# mcu.net
KiCad netlist of a schematic drawn in Altium Designer
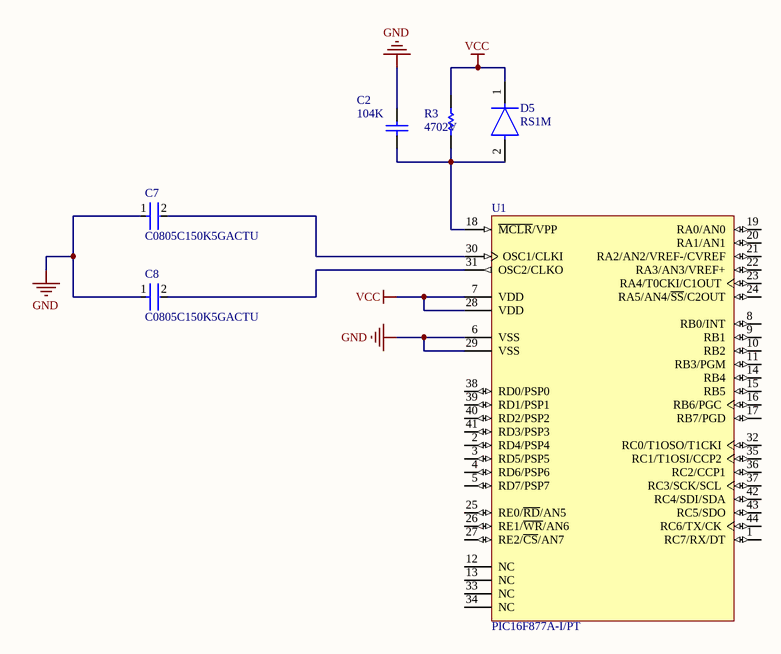
[diagram p0: mcu.SchDoc]

(export (version "E")
  (design (tool "Eeschema 10.0.6"))
  (components
    (comp (ref "C2")
      (value "104K")
      (footprint "CAPC2013X88X50NL20T25")
      (fields (field (name "PART NUMBER") "C0805C104K5RACTU") (field (name "MANUFACTURER") "Kemet"))
      (libsource (lib "Altium Content Vault") (part "CAP"))
    )
    (comp (ref "C7")
      (value "C0805C150K5GACTU")
      (footprint "FP-C0805C-DN-MFG")
      (description "CAP CER 15PF 50V 10% NP0 0805")
      (fields
        (field (name "MANUFACTURER") "KEMET")
        (field (name "OCTOPART") "https://octopart.com/c0805c150k5gactu-kemet-6813460")
      )
      (libsource (lib "Altium Content Vault") (part "b4654b650e69147ec39a6b967a45e02"))
    )
    (comp (ref "C8")
      (value "C0805C150K5GACTU")
      (footprint "FP-C0805C-DN-MFG")
      (description "CAP CER 15PF 50V 10% NP0 0805")
      (fields
        (field (name "MANUFACTURER") "KEMET")
        (field (name "OCTOPART") "https://octopart.com/c0805c150k5gactu-kemet-6813460")
      )
      (libsource (lib "Altium Content Vault") (part "b4654b650e69147ec39a6b967a45e02"))
    )
    (comp (ref "D5")
      (value "RS1M")
      (footprint "FP-403AE-MFG")
      (description "DIODE GEN PURP 1KV 1A SMA")
      (fields
        (field (name "OCTOPART") "https://octopart.com/rs1m-on+semiconductor-84331238")
        (field (name "MANUFACTURER") "ON Semiconductor")
      )
      (libsource (lib "Altium Content Vault") (part "d7152d700b627762746794eb795d46e"))
    )
    (comp (ref "R3")
      (value "4702V")
      (footprint "RESC2013X70X40LL20T20")
      (fields (field (name "MANUFACTURER") "Panasonic") (field (name "PART NUMBER") "ERJ6ENF4702V"))
      (libsource (lib "Altium Content Vault") (part "RES"))
    )
    (comp (ref "U1")
      (value "PIC16F877A-I/PT")
      (footprint "TQFP-PT44_M")
      (libsource (lib "Altium Content Vault") (part "MC-8B-16F874A-SQ44B"))
    )
  )
  (nets
    (net (code "1") (name "GND") (class "Default")
      (node (ref "C2") (pin "2") (pinfunction "2_2") (pintype "passive"))
      (node (ref "C7") (pin "1") (pinfunction "1_1") (pintype "passive"))
      (node (ref "C8") (pin "1") (pinfunction "1_1") (pintype "passive"))
      (node (ref "U1") (pin "29") (pinfunction "VSS_29") (pintype "power_in"))
      (node (ref "U1") (pin "6") (pinfunction "VSS_6") (pintype "power_in"))
    )
    (net (code "2") (name "Net-(D5-A)") (class "Default")
      (node (ref "C2") (pin "1") (pinfunction "1_1") (pintype "passive"))
      (node (ref "D5") (pin "2") (pinfunction "A_2") (pintype "passive"))
      (node (ref "R3") (pin "1") (pinfunction "1_1") (pintype "passive"))
      (node (ref "U1") (pin "18") (pinfunction "~{MCLR}/VPP_18") (pintype "input"))
    )
    (net (code "3") (name "Net-(U1-OSC1{slash}CLKI)") (class "Default")
      (node (ref "C7") (pin "2") (pinfunction "2_2") (pintype "passive"))
      (node (ref "U1") (pin "30") (pinfunction "OSC1/CLKI_30") (pintype "input"))
    )
    (net (code "4") (name "Net-(U1-OSC2{slash}CLKO)") (class "Default")
      (node (ref "C8") (pin "2") (pinfunction "2_2") (pintype "passive"))
      (node (ref "U1") (pin "31") (pinfunction "OSC2/CLKO_31") (pintype "output"))
    )
    (net (code "5") (name "VCC") (class "Default")
      (node (ref "D5") (pin "1") (pinfunction "C_1") (pintype "passive"))
      (node (ref "R3") (pin "2") (pinfunction "2_2") (pintype "passive"))
      (node (ref "U1") (pin "28") (pinfunction "VDD_28") (pintype "power_in"))
      (node (ref "U1") (pin "7") (pinfunction "VDD_7") (pintype "power_in"))
    )
    (net (code "6") (name "unconnected-(U1-NC-Pad12)") (class "Default")
      (node (ref "U1") (pin "12") (pinfunction "NC_12") (pintype "passive"))
    )
    (net (code "7") (name "unconnected-(U1-NC-Pad13)") (class "Default")
      (node (ref "U1") (pin "13") (pinfunction "NC_13") (pintype "passive"))
    )
    (net (code "8") (name "unconnected-(U1-NC-Pad33)") (class "Default")
      (node (ref "U1") (pin "33") (pinfunction "NC_33") (pintype "passive"))
    )
    (net (code "9") (name "unconnected-(U1-NC-Pad34)") (class "Default")
      (node (ref "U1") (pin "34") (pinfunction "NC_34") (pintype "passive"))
    )
    (net (code "10") (name "unconnected-(U1-RA0{slash}AN0-Pad19)") (class "Default")
      (node (ref "U1") (pin "19") (pinfunction "RA0/AN0_19") (pintype "bidirectional"))
    )
    (net (code "11") (name "unconnected-(U1-RA1{slash}AN1-Pad20)") (class "Default")
      (node (ref "U1") (pin "20") (pinfunction "RA1/AN1_20") (pintype "bidirectional"))
    )
    (net (code "12") (name "unconnected-(U1-RA2{slash}AN2{slash}VREF-{slash}CVREF-Pad21)") (class "Default")
      (node (ref "U1") (pin "21") (pinfunction "RA2/AN2/VREF-/CVREF_21") (pintype "bidirectional"))
    )
    (net (code "13") (name "unconnected-(U1-RA3{slash}AN3{slash}VREF+-Pad22)") (class "Default")
      (node (ref "U1") (pin "22") (pinfunction "RA3/AN3/VREF+_22") (pintype "bidirectional"))
    )
    (net (code "14") (name "unconnected-(U1-RA4{slash}T0CKI{slash}C1OUT-Pad23)") (class "Default")
      (node (ref "U1") (pin "23") (pinfunction "RA4/T0CKI/C1OUT_23") (pintype "bidirectional"))
    )
    (net (code "15") (name "unconnected-(U1-RA5{slash}AN4{slash}~{SS}{slash}C2OUT-Pad24)") (class "Default")
      (node (ref "U1") (pin "24") (pinfunction "RA5/AN4/~{SS}/C2OUT_24") (pintype "bidirectional"))
    )
    (net (code "16") (name "unconnected-(U1-RB0{slash}INT-Pad8)") (class "Default")
      (node (ref "U1") (pin "8") (pinfunction "RB0/INT_8") (pintype "bidirectional"))
    )
    (net (code "17") (name "unconnected-(U1-RB1-Pad9)") (class "Default")
      (node (ref "U1") (pin "9") (pinfunction "RB1_9") (pintype "bidirectional"))
    )
    (net (code "18") (name "unconnected-(U1-RB2-Pad10)") (class "Default")
      (node (ref "U1") (pin "10") (pinfunction "RB2_10") (pintype "bidirectional"))
    )
    (net (code "19") (name "unconnected-(U1-RB3{slash}PGM-Pad11)") (class "Default")
      (node (ref "U1") (pin "11") (pinfunction "RB3/PGM_11") (pintype "bidirectional"))
    )
    (net (code "20") (name "unconnected-(U1-RB4-Pad14)") (class "Default")
      (node (ref "U1") (pin "14") (pinfunction "RB4_14") (pintype "bidirectional"))
    )
    (net (code "21") (name "unconnected-(U1-RB5-Pad15)") (class "Default")
      (node (ref "U1") (pin "15") (pinfunction "RB5_15") (pintype "bidirectional"))
    )
    (net (code "22") (name "unconnected-(U1-RB6{slash}PGC-Pad16)") (class "Default")
      (node (ref "U1") (pin "16") (pinfunction "RB6/PGC_16") (pintype "bidirectional"))
    )
    (net (code "23") (name "unconnected-(U1-RB7{slash}PGD-Pad17)") (class "Default")
      (node (ref "U1") (pin "17") (pinfunction "RB7/PGD_17") (pintype "bidirectional"))
    )
    (net (code "24") (name "unconnected-(U1-RC0{slash}T1OSO{slash}T1CKI-Pad32)") (class "Default")
      (node (ref "U1") (pin "32") (pinfunction "RC0/T1OSO/T1CKI_32") (pintype "bidirectional"))
    )
    (net (code "25") (name "unconnected-(U1-RC1{slash}T1OSI{slash}CCP2-Pad35)") (class "Default")
      (node (ref "U1") (pin "35") (pinfunction "RC1/T1OSI/CCP2_35") (pintype "bidirectional"))
    )
    (net (code "26") (name "unconnected-(U1-RC2{slash}CCP1-Pad36)") (class "Default")
      (node (ref "U1") (pin "36") (pinfunction "RC2/CCP1_36") (pintype "bidirectional"))
    )
    (net (code "27") (name "unconnected-(U1-RC3{slash}SCK{slash}SCL-Pad37)") (class "Default")
      (node (ref "U1") (pin "37") (pinfunction "RC3/SCK/SCL_37") (pintype "bidirectional"))
    )
    (net (code "28") (name "unconnected-(U1-RC4{slash}SDI{slash}SDA-Pad42)") (class "Default")
      (node (ref "U1") (pin "42") (pinfunction "RC4/SDI/SDA_42") (pintype "bidirectional"))
    )
    (net (code "29") (name "unconnected-(U1-RC5{slash}SDO-Pad43)") (class "Default")
      (node (ref "U1") (pin "43") (pinfunction "RC5/SDO_43") (pintype "bidirectional"))
    )
    (net (code "30") (name "unconnected-(U1-RC6{slash}TX{slash}CK-Pad44)") (class "Default")
      (node (ref "U1") (pin "44") (pinfunction "RC6/TX/CK_44") (pintype "bidirectional"))
    )
    (net (code "31") (name "unconnected-(U1-RC7{slash}RX{slash}DT-Pad1)") (class "Default")
      (node (ref "U1") (pin "1") (pinfunction "RC7/RX/DT_1") (pintype "bidirectional"))
    )
    (net (code "32") (name "unconnected-(U1-RD0{slash}PSP0-Pad38)") (class "Default")
      (node (ref "U1") (pin "38") (pinfunction "RD0/PSP0_38") (pintype "bidirectional"))
    )
    (net (code "33") (name "unconnected-(U1-RD1{slash}PSP1-Pad39)") (class "Default")
      (node (ref "U1") (pin "39") (pinfunction "RD1/PSP1_39") (pintype "bidirectional"))
    )
    (net (code "34") (name "unconnected-(U1-RD2{slash}PSP2-Pad40)") (class "Default")
      (node (ref "U1") (pin "40") (pinfunction "RD2/PSP2_40") (pintype "bidirectional"))
    )
    (net (code "35") (name "unconnected-(U1-RD3{slash}PSP3-Pad41)") (class "Default")
      (node (ref "U1") (pin "41") (pinfunction "RD3/PSP3_41") (pintype "bidirectional"))
    )
    (net (code "36") (name "unconnected-(U1-RD4{slash}PSP4-Pad2)") (class "Default")
      (node (ref "U1") (pin "2") (pinfunction "RD4/PSP4_2") (pintype "bidirectional"))
    )
    (net (code "37") (name "unconnected-(U1-RD5{slash}PSP5-Pad3)") (class "Default")
      (node (ref "U1") (pin "3") (pinfunction "RD5/PSP5_3") (pintype "bidirectional"))
    )
    (net (code "38") (name "unconnected-(U1-RD6{slash}PSP6-Pad4)") (class "Default")
      (node (ref "U1") (pin "4") (pinfunction "RD6/PSP6_4") (pintype "bidirectional"))
    )
    (net (code "39") (name "unconnected-(U1-RD7{slash}PSP7-Pad5)") (class "Default")
      (node (ref "U1") (pin "5") (pinfunction "RD7/PSP7_5") (pintype "bidirectional"))
    )
    (net (code "40") (name "unconnected-(U1-RE0{slash}~{RD}{slash}AN5-Pad25)") (class "Default")
      (node (ref "U1") (pin "25") (pinfunction "RE0/~{RD}/AN5_25") (pintype "bidirectional"))
    )
    (net (code "41") (name "unconnected-(U1-RE1{slash}~{WR}{slash}AN6-Pad26)") (class "Default")
      (node (ref "U1") (pin "26") (pinfunction "RE1/~{WR}/AN6_26") (pintype "bidirectional"))
    )
    (net (code "42") (name "unconnected-(U1-RE2{slash}~{CS}{slash}AN7-Pad27)") (class "Default")
      (node (ref "U1") (pin "27") (pinfunction "RE2/~{CS}/AN7_27") (pintype "bidirectional"))
    )
  )
)
